# Sheet4.net
KiCad netlist of a schematic drawn in Altium Designer
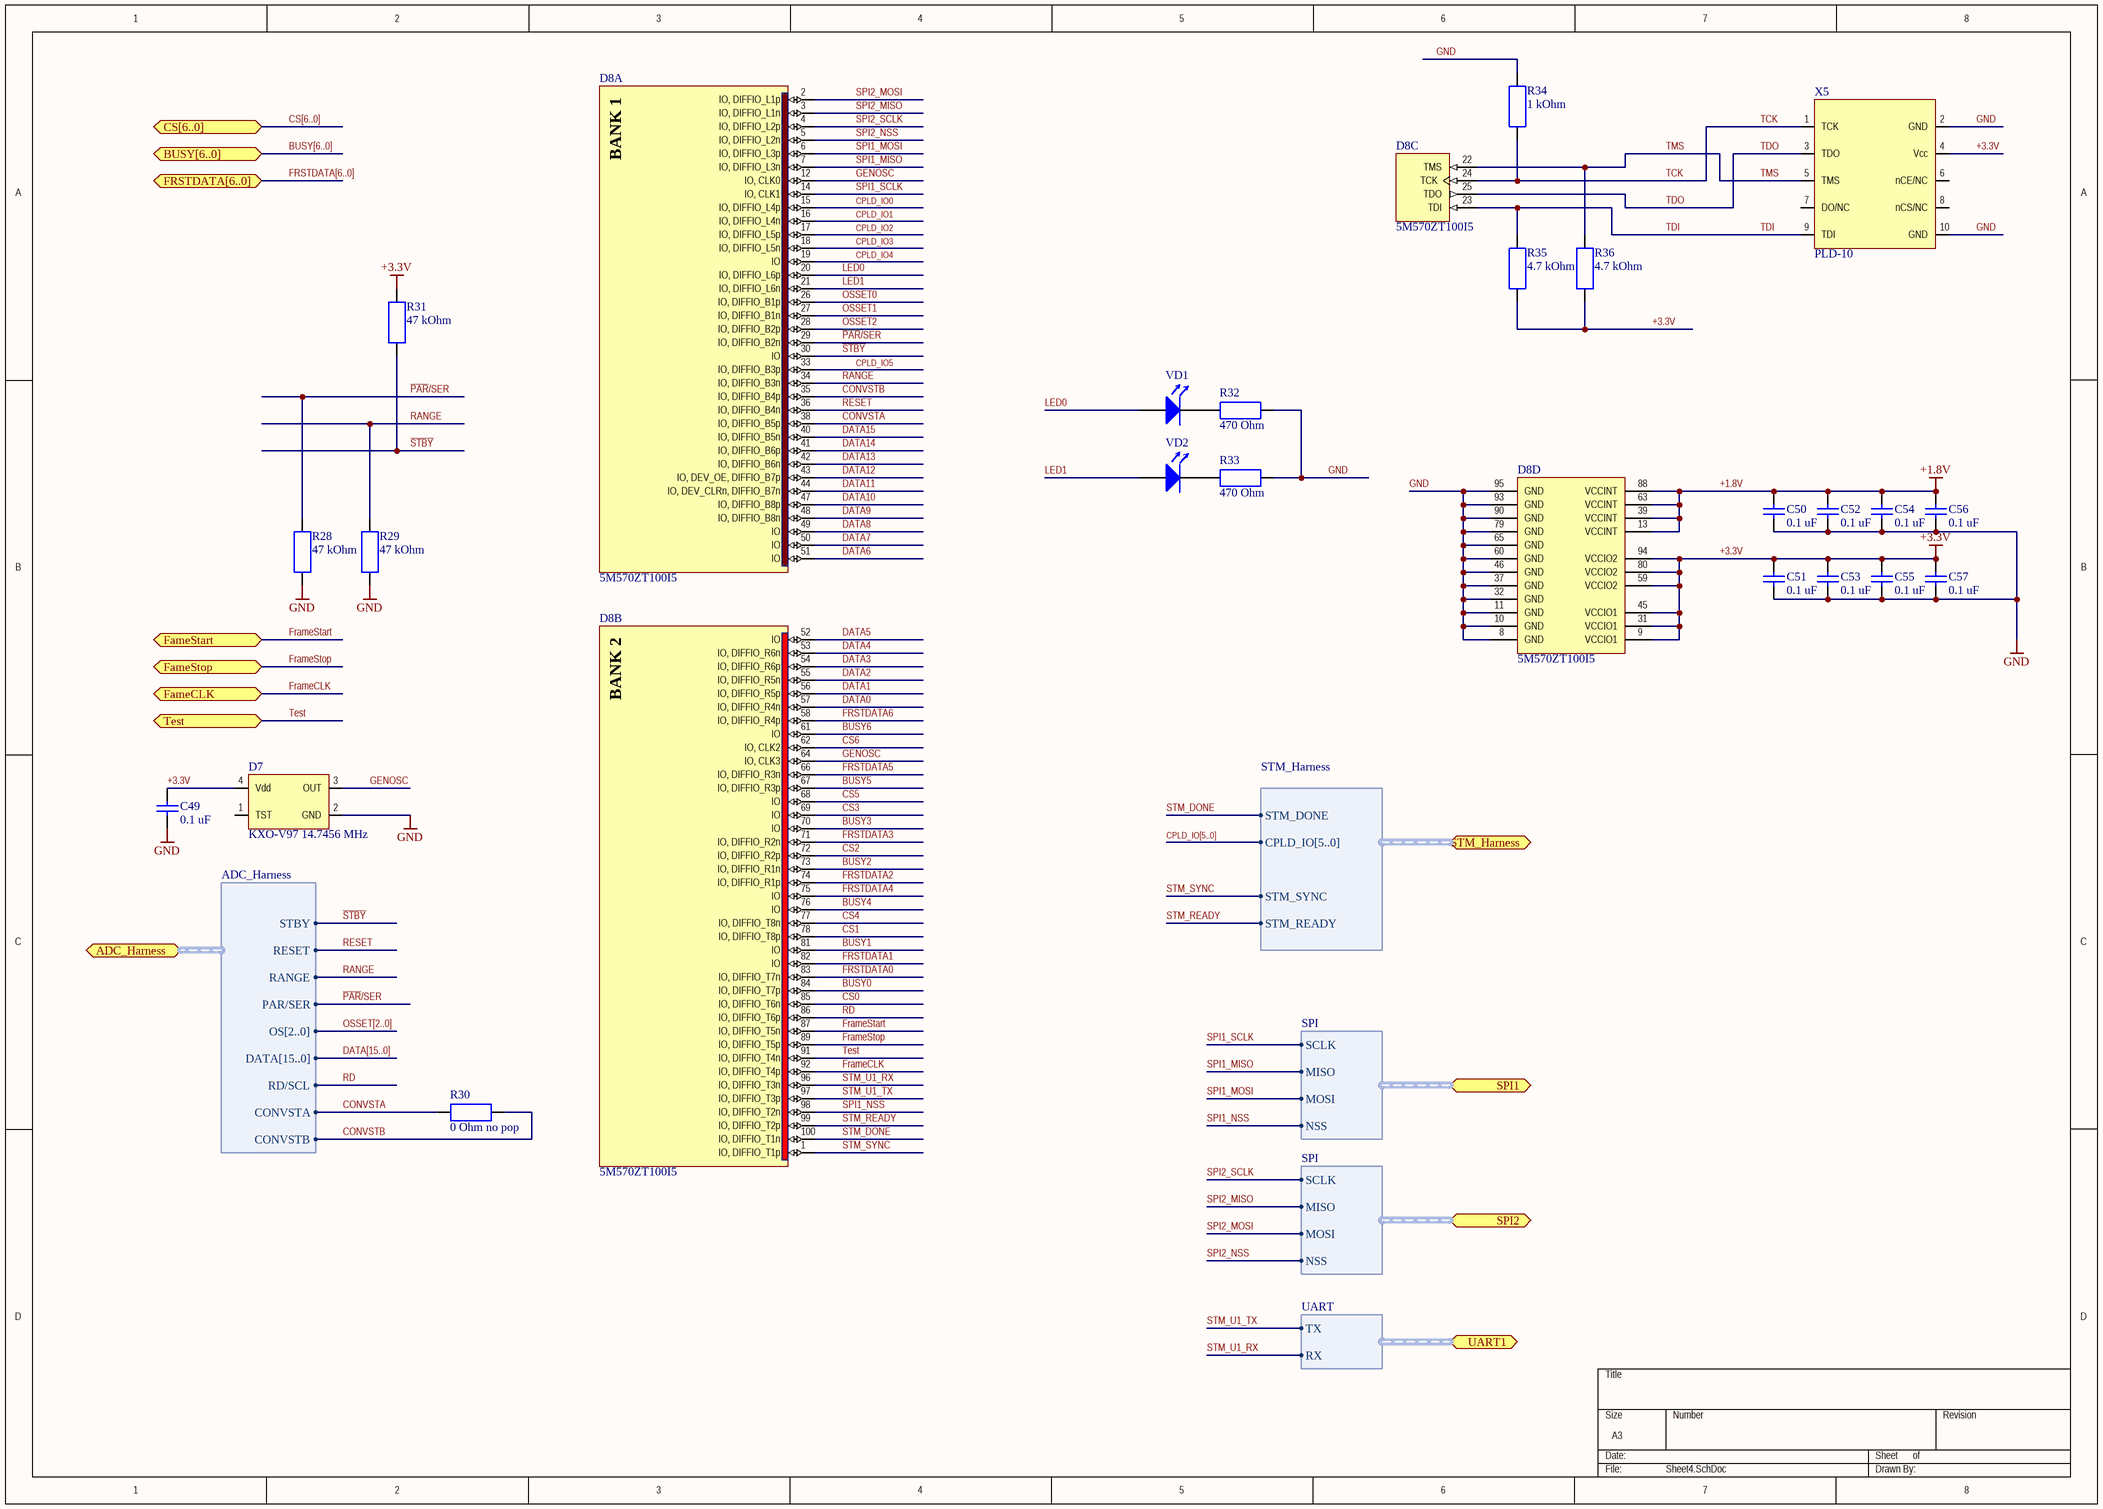
[diagram p0: Sheet4.SchDoc]

(export (version "E")
  (design (tool "Eeschema 10.0.6"))
  (components
    (comp (ref "C49")
      (value "0.1 uF")
      (footprint "CAPC1608N")
      (description "±10%, X7R, 0603")
      (fields (field (name "PUBLISHER") "DS"))
      (libsource (lib "ADClib") (part "CC0603"))
    )
    (comp (ref "C50")
      (value "0.1 uF")
      (footprint "CAPC1608N")
      (description "±10%, X7R, 0603")
      (fields (field (name "PUBLISHER") "DS"))
      (libsource (lib "ADClib") (part "CC0603"))
    )
    (comp (ref "C51")
      (value "0.1 uF")
      (footprint "CAPC1608N")
      (description "±10%, X7R, 0603")
      (fields (field (name "PUBLISHER") "DS"))
      (libsource (lib "ADClib") (part "CC0603"))
    )
    (comp (ref "C52")
      (value "0.1 uF")
      (footprint "CAPC1608N")
      (description "±10%, X7R, 0603")
      (fields (field (name "PUBLISHER") "DS"))
      (libsource (lib "ADClib") (part "CC0603"))
    )
    (comp (ref "C53")
      (value "0.1 uF")
      (footprint "CAPC1608N")
      (description "±10%, X7R, 0603")
      (fields (field (name "PUBLISHER") "DS"))
      (libsource (lib "ADClib") (part "CC0603"))
    )
    (comp (ref "C54")
      (value "0.1 uF")
      (footprint "CAPC1608N")
      (description "±10%, X7R, 0603")
      (fields (field (name "PUBLISHER") "DS"))
      (libsource (lib "ADClib") (part "CC0603"))
    )
    (comp (ref "C55")
      (value "0.1 uF")
      (footprint "CAPC1608N")
      (description "±10%, X7R, 0603")
      (fields (field (name "PUBLISHER") "DS"))
      (libsource (lib "ADClib") (part "CC0603"))
    )
    (comp (ref "C56")
      (value "0.1 uF")
      (footprint "CAPC1608N")
      (description "±10%, X7R, 0603")
      (fields (field (name "PUBLISHER") "DS"))
      (libsource (lib "ADClib") (part "CC0603"))
    )
    (comp (ref "C57")
      (value "0.1 uF")
      (footprint "CAPC1608N")
      (description "±10%, X7R, 0603")
      (fields (field (name "PUBLISHER") "DS"))
      (libsource (lib "ADClib") (part "CC0603"))
    )
    (comp (ref "D7")
      (value "KXO-V97 14.7456 MHz")
      (footprint "KXO-V97")
      (libsource (lib "ADClib") (part "KXO-V97 14.7456 MHz"))
    )
    (comp (ref "D8")
      (value "5M570ZT100I5")
      (footprint "TQFP100_A-120_L")
      (description "MAX V 1.8V CPLD, 74 IOs, 570 Logic Elements, 100-Pin TQFP, Industrial Temperature, Speed Grade 5")
      (libsource (lib "") (part "5M570ZT100I5_1"))
    )
    (comp (ref "R28")
      (value "47 kOhm")
      (footprint "RESC1608N")
      (description "±5%, 0603")
      (fields (field (name "PUBLISHER") "DS"))
      (libsource (lib "ADClib") (part "RES0603"))
    )
    (comp (ref "R29")
      (value "47 kOhm")
      (footprint "RESC1608N")
      (description "±5%, 0603")
      (fields (field (name "PUBLISHER") "DS"))
      (libsource (lib "ADClib") (part "RES0603"))
    )
    (comp (ref "R30")
      (value "0 Ohm no pop")
      (footprint "RESC1608N")
      (description "±5%, 0603")
      (fields (field (name "PUBLISHER") "DS"))
      (libsource (lib "ADClib") (part "RES0603"))
    )
    (comp (ref "R31")
      (value "47 kOhm")
      (footprint "RESC1608N")
      (description "±5%, 0603")
      (fields (field (name "PUBLISHER") "DS"))
      (libsource (lib "ADClib") (part "RES0603"))
    )
    (comp (ref "R32")
      (value "470 Ohm")
      (footprint "RESC1608N")
      (description "±5%, 0603")
      (fields (field (name "PUBLISHER") "DS"))
      (libsource (lib "ADClib") (part "RES0603"))
    )
    (comp (ref "R33")
      (value "470 Ohm")
      (footprint "RESC1608N")
      (description "±5%, 0603")
      (fields (field (name "PUBLISHER") "DS"))
      (libsource (lib "ADClib") (part "RES0603"))
    )
    (comp (ref "R34")
      (value "1 kOhm")
      (footprint "RESC1608N")
      (description "±5%, 0603")
      (fields (field (name "PUBLISHER") "DS"))
      (libsource (lib "ADClib") (part "RES0603"))
    )
    (comp (ref "R35")
      (value "4.7 kOhm")
      (footprint "RESC1608N")
      (description "±5%, 0603")
      (fields (field (name "PUBLISHER") "DS"))
      (libsource (lib "ADClib") (part "RES0603"))
    )
    (comp (ref "R36")
      (value "4.7 kOhm")
      (footprint "RESC1608N")
      (description "±5%, 0603")
      (fields (field (name "PUBLISHER") "DS"))
      (libsource (lib "ADClib") (part "RES0603"))
    )
    (comp (ref "VD1")
      (value "KP-1608SURC")
      (footprint "LED1608N")
      (fields (field (name "PUBLISHER") "Altium Limited"))
      (libsource (lib "ADClib") (part "KP-1608SURC"))
    )
    (comp (ref "VD2")
      (value "KP-1608SURC")
      (footprint "LED1608N")
      (fields (field (name "PUBLISHER") "Altium Limited"))
      (libsource (lib "ADClib") (part "KP-1608SURC"))
    )
    (comp (ref "X5") (value "PLD-10") (footprint "PLD-10") (libsource (lib "ADClib") (part "BYTEBLASTER")))
  )
  (nets
    (net (code "5") (name "+1.8V") (class "Default")
      (node (ref "C50") (pin "2") (pinfunction "2_2") (pintype "passive"))
      (node (ref "C52") (pin "2") (pinfunction "2_2") (pintype "passive"))
      (node (ref "C54") (pin "2") (pinfunction "2_2") (pintype "passive"))
      (node (ref "C56") (pin "2") (pinfunction "2_2") (pintype "passive"))
      (node (ref "D8") (pin "13") (pinfunction "VCCINT_13") (pintype "power_in"))
      (node (ref "D8") (pin "39") (pinfunction "VCCINT_39") (pintype "power_in"))
      (node (ref "D8") (pin "63") (pinfunction "VCCINT_63") (pintype "power_in"))
      (node (ref "D8") (pin "88") (pinfunction "VCCINT_88") (pintype "power_in"))
    )
    (net (code "6") (name "+3.3V") (class "Default")
      (node (ref "C49") (pin "2") (pinfunction "2_2") (pintype "passive"))
      (node (ref "C51") (pin "2") (pinfunction "2_2") (pintype "passive"))
      (node (ref "C53") (pin "2") (pinfunction "2_2") (pintype "passive"))
      (node (ref "C55") (pin "2") (pinfunction "2_2") (pintype "passive"))
      (node (ref "C57") (pin "2") (pinfunction "2_2") (pintype "passive"))
      (node (ref "D7") (pin "4") (pinfunction "Vdd_4") (pintype "passive"))
      (node (ref "D8") (pin "31") (pinfunction "VCCIO1_31") (pintype "power_in"))
      (node (ref "D8") (pin "45") (pinfunction "VCCIO1_45") (pintype "power_in"))
      (node (ref "D8") (pin "59") (pinfunction "VCCIO2_59") (pintype "power_in"))
      (node (ref "D8") (pin "80") (pinfunction "VCCIO2_80") (pintype "power_in"))
      (node (ref "D8") (pin "9") (pinfunction "VCCIO1_9") (pintype "power_in"))
      (node (ref "D8") (pin "94") (pinfunction "VCCIO2_94") (pintype "power_in"))
      (node (ref "R31") (pin "2") (pinfunction "2_2") (pintype "passive"))
      (node (ref "R35") (pin "2") (pinfunction "2_2") (pintype "passive"))
      (node (ref "R36") (pin "2") (pinfunction "2_2") (pintype "passive"))
      (node (ref "X5") (pin "4") (pinfunction "Vcc_4") (pintype "passive"))
    )
    (net (code "8") (name "/BUSY0") (class "Default")
      (node (ref "D8") (pin "84") (pinfunction "IO,_DIFFIO_T7p_84") (pintype "bidirectional"))
    )
    (net (code "9") (name "/BUSY1") (class "Default")
      (node (ref "D8") (pin "81") (pinfunction "IO_81") (pintype "bidirectional"))
    )
    (net (code "10") (name "/BUSY2") (class "Default")
      (node (ref "D8") (pin "73") (pinfunction "IO,_DIFFIO_R1n_73") (pintype "bidirectional"))
    )
    (net (code "11") (name "/BUSY3") (class "Default")
      (node (ref "D8") (pin "70") (pinfunction "IO_70") (pintype "bidirectional"))
    )
    (net (code "12") (name "/BUSY4") (class "Default")
      (node (ref "D8") (pin "76") (pinfunction "IO_76") (pintype "bidirectional"))
    )
    (net (code "13") (name "/BUSY5") (class "Default")
      (node (ref "D8") (pin "67") (pinfunction "IO,_DIFFIO_R3p_67") (pintype "bidirectional"))
    )
    (net (code "14") (name "/BUSY6") (class "Default")
      (node (ref "D8") (pin "61") (pinfunction "IO_61") (pintype "bidirectional"))
    )
    (net (code "16") (name "/CONVSTA") (class "Default")
      (node (ref "D8") (pin "38") (pinfunction "IO,_DIFFIO_B5p_38") (pintype "bidirectional"))
      (node (ref "R30") (pin "2") (pinfunction "2_2") (pintype "passive"))
    )
    (net (code "17") (name "/CONVSTB") (class "Default")
      (node (ref "D8") (pin "35") (pinfunction "IO,_DIFFIO_B4p_35") (pintype "bidirectional"))
      (node (ref "R30") (pin "1") (pinfunction "1_1") (pintype "passive"))
    )
    (net (code "18") (name "/CPLD_IO0") (class "Default")
      (node (ref "D8") (pin "15") (pinfunction "IO,_DIFFIO_L4p_15") (pintype "bidirectional"))
    )
    (net (code "19") (name "/CPLD_IO1") (class "Default")
      (node (ref "D8") (pin "16") (pinfunction "IO,_DIFFIO_L4n_16") (pintype "bidirectional"))
    )
    (net (code "20") (name "/CPLD_IO2") (class "Default")
      (node (ref "D8") (pin "17") (pinfunction "IO,_DIFFIO_L5p_17") (pintype "bidirectional"))
    )
    (net (code "21") (name "/CPLD_IO3") (class "Default")
      (node (ref "D8") (pin "18") (pinfunction "IO,_DIFFIO_L5n_18") (pintype "bidirectional"))
    )
    (net (code "22") (name "/CPLD_IO4") (class "Default")
      (node (ref "D8") (pin "19") (pinfunction "IO_19") (pintype "bidirectional"))
    )
    (net (code "23") (name "/CPLD_IO5") (class "Default")
      (node (ref "D8") (pin "33") (pinfunction "IO,_DIFFIO_B3p_33") (pintype "bidirectional"))
    )
    (net (code "24") (name "/CS0") (class "Default")
      (node (ref "D8") (pin "85") (pinfunction "IO,_DIFFIO_T6n_85") (pintype "bidirectional"))
    )
    (net (code "25") (name "/CS1") (class "Default")
      (node (ref "D8") (pin "78") (pinfunction "IO,_DIFFIO_T8p_78") (pintype "bidirectional"))
    )
    (net (code "26") (name "/CS2") (class "Default")
      (node (ref "D8") (pin "72") (pinfunction "IO,_DIFFIO_R2p_72") (pintype "bidirectional"))
    )
    (net (code "27") (name "/CS3") (class "Default")
      (node (ref "D8") (pin "69") (pinfunction "IO_69") (pintype "bidirectional"))
    )
    (net (code "28") (name "/CS4") (class "Default")
      (node (ref "D8") (pin "77") (pinfunction "IO,_DIFFIO_T8n_77") (pintype "bidirectional"))
    )
    (net (code "29") (name "/CS5") (class "Default")
      (node (ref "D8") (pin "68") (pinfunction "IO_68") (pintype "bidirectional"))
    )
    (net (code "30") (name "/CS6") (class "Default")
      (node (ref "D8") (pin "62") (pinfunction "IO,_CLK2_62") (pintype "bidirectional"))
    )
    (net (code "32") (name "/DATA0") (class "Default")
      (node (ref "D8") (pin "57") (pinfunction "IO,_DIFFIO_R4n_57") (pintype "bidirectional"))
    )
    (net (code "33") (name "/DATA1") (class "Default")
      (node (ref "D8") (pin "56") (pinfunction "IO,_DIFFIO_R5p_56") (pintype "bidirectional"))
    )
    (net (code "34") (name "/DATA2") (class "Default")
      (node (ref "D8") (pin "55") (pinfunction "IO,_DIFFIO_R5n_55") (pintype "bidirectional"))
    )
    (net (code "35") (name "/DATA3") (class "Default")
      (node (ref "D8") (pin "54") (pinfunction "IO,_DIFFIO_R6p_54") (pintype "bidirectional"))
    )
    (net (code "36") (name "/DATA4") (class "Default")
      (node (ref "D8") (pin "53") (pinfunction "IO,_DIFFIO_R6n_53") (pintype "bidirectional"))
    )
    (net (code "37") (name "/DATA5") (class "Default")
      (node (ref "D8") (pin "52") (pinfunction "IO_52") (pintype "bidirectional"))
    )
    (net (code "38") (name "/DATA6") (class "Default")
      (node (ref "D8") (pin "51") (pinfunction "IO_51") (pintype "bidirectional"))
    )
    (net (code "39") (name "/DATA7") (class "Default")
      (node (ref "D8") (pin "50") (pinfunction "IO_50") (pintype "bidirectional"))
    )
    (net (code "40") (name "/DATA8") (class "Default")
      (node (ref "D8") (pin "49") (pinfunction "IO_49") (pintype "bidirectional"))
    )
    (net (code "41") (name "/DATA9") (class "Default")
      (node (ref "D8") (pin "48") (pinfunction "IO,_DIFFIO_B8n_48") (pintype "bidirectional"))
    )
    (net (code "42") (name "/DATA10") (class "Default")
      (node (ref "D8") (pin "47") (pinfunction "IO,_DIFFIO_B8p_47") (pintype "bidirectional"))
    )
    (net (code "43") (name "/DATA11") (class "Default")
      (node (ref "D8") (pin "44") (pinfunction "IO,_DEV_CLRn,_DIFFIO_B7n_44") (pintype "bidirectional"))
    )
    (net (code "44") (name "/DATA12") (class "Default")
      (node (ref "D8") (pin "43") (pinfunction "IO,_DEV_OE,_DIFFIO_B7p_43") (pintype "bidirectional"))
    )
    (net (code "45") (name "/DATA13") (class "Default")
      (node (ref "D8") (pin "42") (pinfunction "IO,_DIFFIO_B6n_42") (pintype "bidirectional"))
    )
    (net (code "46") (name "/DATA14") (class "Default")
      (node (ref "D8") (pin "41") (pinfunction "IO,_DIFFIO_B6p_41") (pintype "bidirectional"))
    )
    (net (code "47") (name "/DATA15") (class "Default")
      (node (ref "D8") (pin "40") (pinfunction "IO,_DIFFIO_B5n_40") (pintype "bidirectional"))
    )
    (net (code "49") (name "/FRSTDATA0") (class "Default")
      (node (ref "D8") (pin "83") (pinfunction "IO,_DIFFIO_T7n_83") (pintype "bidirectional"))
    )
    (net (code "50") (name "/FRSTDATA1") (class "Default")
      (node (ref "D8") (pin "82") (pinfunction "IO_82") (pintype "bidirectional"))
    )
    (net (code "51") (name "/FRSTDATA2") (class "Default")
      (node (ref "D8") (pin "74") (pinfunction "IO,_DIFFIO_R1p_74") (pintype "bidirectional"))
    )
    (net (code "52") (name "/FRSTDATA3") (class "Default")
      (node (ref "D8") (pin "71") (pinfunction "IO,_DIFFIO_R2n_71") (pintype "bidirectional"))
    )
    (net (code "53") (name "/FRSTDATA4") (class "Default")
      (node (ref "D8") (pin "75") (pinfunction "IO_75") (pintype "bidirectional"))
    )
    (net (code "54") (name "/FRSTDATA5") (class "Default")
      (node (ref "D8") (pin "66") (pinfunction "IO,_DIFFIO_R3n_66") (pintype "bidirectional"))
    )
    (net (code "55") (name "/FRSTDATA6") (class "Default")
      (node (ref "D8") (pin "58") (pinfunction "IO,_DIFFIO_R4p_58") (pintype "bidirectional"))
    )
    (net (code "57") (name "/FrameCLK") (class "Default")
      (node (ref "D8") (pin "92") (pinfunction "IO,_DIFFIO_T4p_92") (pintype "bidirectional"))
    )
    (net (code "58") (name "/FrameStart") (class "Default")
      (node (ref "D8") (pin "87") (pinfunction "IO,_DIFFIO_T5n_87") (pintype "bidirectional"))
    )
    (net (code "59") (name "/FrameStop") (class "Default")
      (node (ref "D8") (pin "89") (pinfunction "IO,_DIFFIO_T5p_89") (pintype "bidirectional"))
    )
    (net (code "60") (name "/GENOSC") (class "Default")
      (node (ref "D7") (pin "3") (pinfunction "OUT_3") (pintype "passive"))
      (node (ref "D8") (pin "12") (pinfunction "IO,_CLK0_12") (pintype "bidirectional"))
      (node (ref "D8") (pin "64") (pinfunction "IO,_CLK3_64") (pintype "bidirectional"))
    )
    (net (code "61") (name "/LED0") (class "Default")
      (node (ref "D8") (pin "20") (pinfunction "IO,_DIFFIO_L6p_20") (pintype "bidirectional"))
      (node (ref "VD1") (pin "1") (pinfunction "A_1") (pintype "passive"))
    )
    (net (code "62") (name "/LED1") (class "Default")
      (node (ref "D8") (pin "21") (pinfunction "IO,_DIFFIO_L6n_21") (pintype "bidirectional"))
      (node (ref "VD2") (pin "1") (pinfunction "A_1") (pintype "passive"))
    )
    (net (code "63") (name "/OSSET0") (class "Default")
      (node (ref "D8") (pin "26") (pinfunction "IO,_DIFFIO_B1p_26") (pintype "bidirectional"))
    )
    (net (code "64") (name "/OSSET1") (class "Default")
      (node (ref "D8") (pin "27") (pinfunction "IO,_DIFFIO_B1n_27") (pintype "bidirectional"))
    )
    (net (code "65") (name "/OSSET2") (class "Default")
      (node (ref "D8") (pin "28") (pinfunction "IO,_DIFFIO_B2p_28") (pintype "bidirectional"))
    )
    (net (code "66") (name "/RANGE") (class "Default")
      (node (ref "D8") (pin "34") (pinfunction "IO,_DIFFIO_B3n_34") (pintype "bidirectional"))
      (node (ref "R29") (pin "2") (pinfunction "2_2") (pintype "passive"))
    )
    (net (code "67") (name "/RD") (class "Default")
      (node (ref "D8") (pin "86") (pinfunction "IO,_DIFFIO_T6p_86") (pintype "bidirectional"))
    )
    (net (code "68") (name "/RESET") (class "Default")
      (node (ref "D8") (pin "36") (pinfunction "IO,_DIFFIO_B4n_36") (pintype "bidirectional"))
    )
    (net (code "69") (name "/SPI1_MISO") (class "Default")
      (node (ref "D8") (pin "7") (pinfunction "IO,_DIFFIO_L3n_7") (pintype "bidirectional"))
    )
    (net (code "70") (name "/SPI1_MOSI") (class "Default")
      (node (ref "D8") (pin "6") (pinfunction "IO,_DIFFIO_L3p_6") (pintype "bidirectional"))
    )
    (net (code "71") (name "/SPI1_NSS") (class "Default")
      (node (ref "D8") (pin "98") (pinfunction "IO,_DIFFIO_T2n_98") (pintype "bidirectional"))
    )
    (net (code "72") (name "/SPI1_SCLK") (class "Default")
      (node (ref "D8") (pin "14") (pinfunction "IO,_CLK1_14") (pintype "bidirectional"))
    )
    (net (code "73") (name "/SPI2_MISO") (class "Default")
      (node (ref "D8") (pin "3") (pinfunction "IO,_DIFFIO_L1n_3") (pintype "bidirectional"))
    )
    (net (code "74") (name "/SPI2_MOSI") (class "Default")
      (node (ref "D8") (pin "2") (pinfunction "IO,_DIFFIO_L1p_2") (pintype "bidirectional"))
    )
    (net (code "75") (name "/SPI2_NSS") (class "Default")
      (node (ref "D8") (pin "5") (pinfunction "IO,_DIFFIO_L2n_5") (pintype "bidirectional"))
    )
    (net (code "76") (name "/SPI2_SCLK") (class "Default")
      (node (ref "D8") (pin "4") (pinfunction "IO,_DIFFIO_L2p_4") (pintype "bidirectional"))
    )
    (net (code "77") (name "/STM_DONE") (class "Default")
      (node (ref "D8") (pin "100") (pinfunction "IO,_DIFFIO_T1n_100") (pintype "bidirectional"))
    )
    (net (code "79") (name "/STM_READY") (class "Default")
      (node (ref "D8") (pin "99") (pinfunction "IO,_DIFFIO_T2p_99") (pintype "bidirectional"))
    )
    (net (code "80") (name "/STM_SYNC") (class "Default")
      (node (ref "D8") (pin "1") (pinfunction "IO,_DIFFIO_T1p_1") (pintype "bidirectional"))
    )
    (net (code "81") (name "/STM_U1_RX") (class "Default")
      (node (ref "D8") (pin "96") (pinfunction "IO,_DIFFIO_T3n_96") (pintype "bidirectional"))
    )
    (net (code "82") (name "/STM_U1_TX") (class "Default")
      (node (ref "D8") (pin "97") (pinfunction "IO,_DIFFIO_T3p_97") (pintype "bidirectional"))
    )
    (net (code "83") (name "/TCK") (class "Default")
      (node (ref "D8") (pin "24") (pinfunction "TCK_24") (pintype "input"))
      (node (ref "R34") (pin "2") (pinfunction "2_2") (pintype "passive"))
      (node (ref "X5") (pin "1") (pinfunction "TCK_1") (pintype "passive"))
    )
    (net (code "84") (name "/TDI") (class "Default")
      (node (ref "D8") (pin "23") (pinfunction "TDI_23") (pintype "input"))
      (node (ref "R35") (pin "1") (pinfunction "1_1") (pintype "passive"))
      (node (ref "X5") (pin "9") (pinfunction "TDI_9") (pintype "passive"))
    )
    (net (code "85") (name "/TDO") (class "Default")
      (node (ref "D8") (pin "25") (pinfunction "TDO_25") (pintype "output"))
      (node (ref "X5") (pin "3") (pinfunction "TDO_3") (pintype "passive"))
    )
    (net (code "86") (name "/TMS") (class "Default")
      (node (ref "D8") (pin "22") (pinfunction "TMS_22") (pintype "input"))
      (node (ref "R36") (pin "1") (pinfunction "1_1") (pintype "passive"))
      (node (ref "X5") (pin "5") (pinfunction "TMS_5") (pintype "passive"))
    )
    (net (code "87") (name "/Test") (class "Default")
      (node (ref "D8") (pin "91") (pinfunction "IO,_DIFFIO_T4n_91") (pintype "bidirectional"))
    )
    (net (code "92") (name "/~{PAR}{slash}SER") (class "Default")
      (node (ref "D8") (pin "29") (pinfunction "IO,_DIFFIO_B2n_29") (pintype "bidirectional"))
      (node (ref "R28") (pin "2") (pinfunction "2_2") (pintype "passive"))
    )
    (net (code "93") (name "/~{STBY}") (class "Default")
      (node (ref "D8") (pin "30") (pinfunction "IO_30") (pintype "bidirectional"))
      (node (ref "R31") (pin "1") (pinfunction "1_1") (pintype "passive"))
    )
    (net (code "94") (name "GND") (class "Default")
      (node (ref "C49") (pin "1") (pinfunction "1_1") (pintype "passive"))
      (node (ref "C50") (pin "1") (pinfunction "1_1") (pintype "passive"))
      (node (ref "C51") (pin "1") (pinfunction "1_1") (pintype "passive"))
      (node (ref "C52") (pin "1") (pinfunction "1_1") (pintype "passive"))
      (node (ref "C53") (pin "1") (pinfunction "1_1") (pintype "passive"))
      (node (ref "C54") (pin "1") (pinfunction "1_1") (pintype "passive"))
      (node (ref "C55") (pin "1") (pinfunction "1_1") (pintype "passive"))
      (node (ref "C56") (pin "1") (pinfunction "1_1") (pintype "passive"))
      (node (ref "C57") (pin "1") (pinfunction "1_1") (pintype "passive"))
      (node (ref "D7") (pin "2") (pinfunction "GND_2") (pintype "passive"))
      (node (ref "D8") (pin "10") (pinfunction "GND_10") (pintype "power_in"))
      (node (ref "D8") (pin "11") (pinfunction "GND_11") (pintype "power_in"))
      (node (ref "D8") (pin "32") (pinfunction "GND_32") (pintype "power_in"))
      (node (ref "D8") (pin "37") (pinfunction "GND_37") (pintype "power_in"))
      (node (ref "D8") (pin "46") (pinfunction "GND_46") (pintype "power_in"))
      (node (ref "D8") (pin "60") (pinfunction "GND_60") (pintype "power_in"))
      (node (ref "D8") (pin "65") (pinfunction "GND_65") (pintype "power_in"))
      (node (ref "D8") (pin "79") (pinfunction "GND_79") (pintype "power_in"))
      (node (ref "D8") (pin "8") (pinfunction "GND_8") (pintype "power_in"))
      (node (ref "D8") (pin "90") (pinfunction "GND_90") (pintype "power_in"))
      (node (ref "D8") (pin "93") (pinfunction "GND_93") (pintype "power_in"))
      (node (ref "D8") (pin "95") (pinfunction "GND_95") (pintype "power_in"))
      (node (ref "R28") (pin "1") (pinfunction "1_1") (pintype "passive"))
      (node (ref "R29") (pin "1") (pinfunction "1_1") (pintype "passive"))
      (node (ref "R32") (pin "2") (pinfunction "2_2") (pintype "passive"))
      (node (ref "R33") (pin "2") (pinfunction "2_2") (pintype "passive"))
      (node (ref "R34") (pin "1") (pinfunction "1_1") (pintype "passive"))
      (node (ref "X5") (pin "10") (pinfunction "GND_10") (pintype "passive"))
      (node (ref "X5") (pin "2") (pinfunction "GND_2") (pintype "passive"))
    )
    (net (code "95") (name "Net-(VD1-K)") (class "Default")
      (node (ref "R32") (pin "1") (pinfunction "1_1") (pintype "passive"))
      (node (ref "VD1") (pin "2") (pinfunction "K_2") (pintype "passive"))
    )
    (net (code "96") (name "Net-(VD2-K)") (class "Default")
      (node (ref "R33") (pin "1") (pinfunction "1_1") (pintype "passive"))
      (node (ref "VD2") (pin "2") (pinfunction "K_2") (pintype "passive"))
    )
    (net (code "97") (name "unconnected-(D7-TST-Pad1)") (class "Default")
      (node (ref "D7") (pin "1") (pinfunction "TST_1") (pintype "passive"))
    )
    (net (code "98") (name "unconnected-(X5-DO{slash}NC-Pad7)") (class "Default")
      (node (ref "X5") (pin "7") (pinfunction "DO/NC_7") (pintype "passive"))
    )
    (net (code "99") (name "unconnected-(X5-nCE{slash}NC-Pad6)") (class "Default")
      (node (ref "X5") (pin "6") (pinfunction "nCE/NC_6") (pintype "passive"))
    )
    (net (code "100") (name "unconnected-(X5-nCS{slash}NC-Pad8)") (class "Default")
      (node (ref "X5") (pin "8") (pinfunction "nCS/NC_8") (pintype "passive"))
    )
  )
)
